# 23D_OLEDisplay_test.net
KiCad netlist of a schematic drawn in Altium Designer
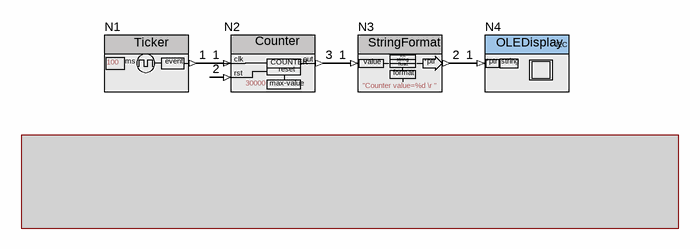
[diagram p0: 23D_OLEDisplay_test.SchDoc]

(export (version "E")
  (design (tool "Eeschema 10.0.6"))
  (components
    (comp (ref "N1")
      (value "Ticker")
      (description "Creates a Periodical Event")
      (fields (field (name "NBLOCKSPARAMETER1") "100"))
      (libsource (lib "studio") (part "NODE-TICKER"))
    )
    (comp (ref "N2")
      (value "Counter")
      (fields (field (name "NBLOCKSPARAMETER1") "30000"))
      (libsource (lib "studio") (part "NODE-COUNTER"))
    )
    (comp (ref "N3")
      (value "StringFormat")
      (fields (field (name "NBLOCKSPARAMETER1") "\"Counter value=%d~{ }r \""))
      (libsource (lib "studio") (part "NODE-STRINGFORMAT"))
    )
    (comp (ref "N4") (value "OLEDisplay") (libsource (lib "studio") (part "NODE-OLEDisplay")))
  )
  (nets
    (net (code "1") (name "Net-(N1-OUT)") (class "Default")
      (node (ref "N1") (pin "1") (pinfunction "OUT_1") (pintype "output"))
      (node (ref "N2") (pin "1") (pinfunction "COUNT-IN_1") (pintype "input"))
    )
    (net (code "2") (name "Net-(N2-OUT)") (class "Default")
      (node (ref "N2") (pin "3") (pinfunction "OUT_3") (pintype "output"))
      (node (ref "N3") (pin "1") (pinfunction "IN_1") (pintype "input"))
    )
    (net (code "3") (name "Net-(N3-OUT)") (class "Default")
      (node (ref "N3") (pin "2") (pinfunction "OUT_2") (pintype "output"))
      (node (ref "N4") (pin "1") (pinfunction "value_1") (pintype "input"))
    )
    (net (code "4") (name "unconnected-(N2-RESET-Pad2)") (class "Default")
      (node (ref "N2") (pin "2") (pinfunction "RESET_2") (pintype "input"))
    )
  )
)
